# Power.net
KiCad netlist of a schematic drawn in Altium Designer
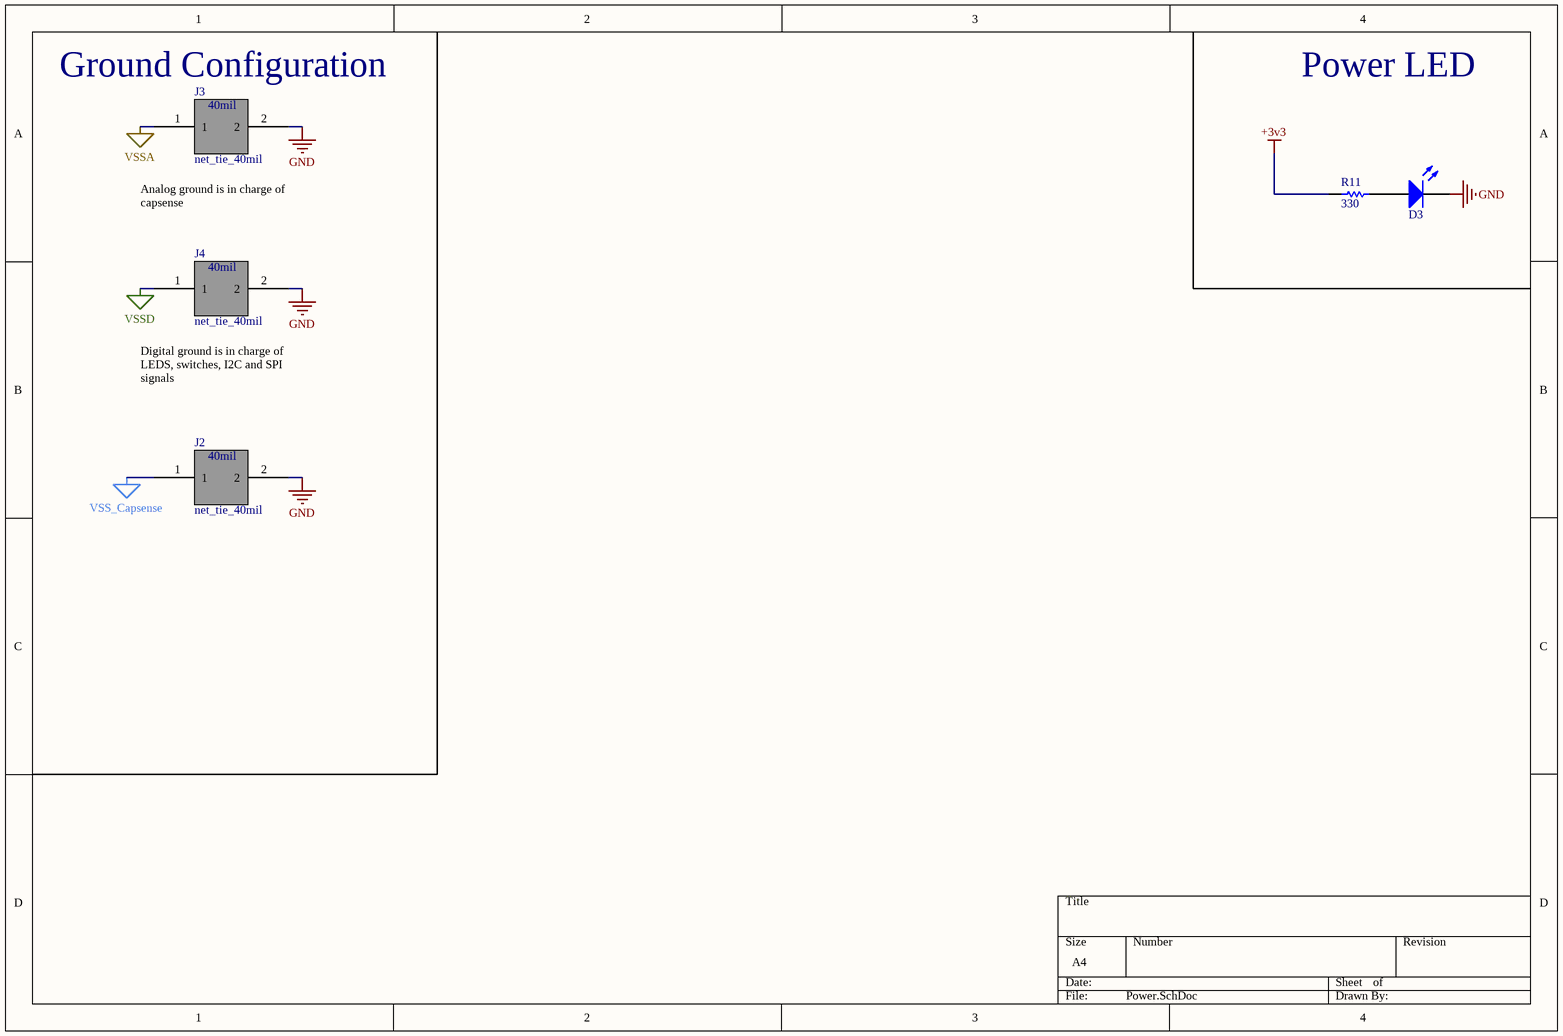
[diagram p0: Power.SchDoc]

(export (version "E")
  (design (tool "Eeschema 10.0.6"))
  (components
    (comp (ref "D3")
      (value "150060BS75000")
      (footprint "0603_A")
      (description "SMD mono-color Chip LED, WL-SMCW, Blue")
      (fields (field (name "MANUFACTURER") "Wuerth Elektronik"))
      (libsource (lib "Altium Content Vault") (part "WE-LED_K1A2-2"))
    )
    (comp (ref "J2")
      (value "net_tie_40mil")
      (footprint "net_tie")
      (libsource (lib "net_ties") (part "net_tie_40mil"))
    )
    (comp (ref "J3")
      (value "net_tie_40mil")
      (footprint "net_tie")
      (libsource (lib "net_ties") (part "net_tie_40mil"))
    )
    (comp (ref "J4")
      (value "net_tie_40mil")
      (footprint "net_tie")
      (libsource (lib "net_ties") (part "net_tie_40mil"))
    )
    (comp (ref "R11")
      (value "330")
      (footprint "RESC0603(1608)_L")
      (description "330R 0.1W 5% 0603 (1608 Metric)  SMD")
      (fields (field (name "TOLERANCE") "5 %") (field (name "POWER") "0.1 W"))
      (libsource (lib "Altium Content Vault") (part "RES"))
    )
  )
  (nets
    (net (code "1") (name "+3v3") (class "Default")
      (node (ref "R11") (pin "1") (pinfunction "1_1") (pintype "passive"))
    )
    (net (code "2") (name "GND") (class "Default")
      (node (ref "D3") (pin "1") (pinfunction "K_1") (pintype "passive"))
      (node (ref "J2") (pin "2") (pinfunction "2_2") (pintype "passive"))
      (node (ref "J3") (pin "2") (pinfunction "2_2") (pintype "passive"))
      (node (ref "J4") (pin "2") (pinfunction "2_2") (pintype "passive"))
    )
    (net (code "3") (name "Net-(D3-A)") (class "Default")
      (node (ref "D3") (pin "2") (pinfunction "A_2") (pintype "passive"))
      (node (ref "R11") (pin "2") (pinfunction "2_2") (pintype "passive"))
    )
    (net (code "4") (name "VSSA") (class "Default")
      (node (ref "J3") (pin "1") (pinfunction "1_1") (pintype "passive"))
    )
    (net (code "5") (name "VSSD") (class "Default")
      (node (ref "J4") (pin "1") (pinfunction "1_1") (pintype "passive"))
    )
    (net (code "6") (name "VSS_Capsense") (class "Default")
      (node (ref "J2") (pin "1") (pinfunction "1_1") (pintype "passive"))
    )
  )
)
